# Blokkskjema.net
KiCad netlist of a schematic drawn in Altium Designer
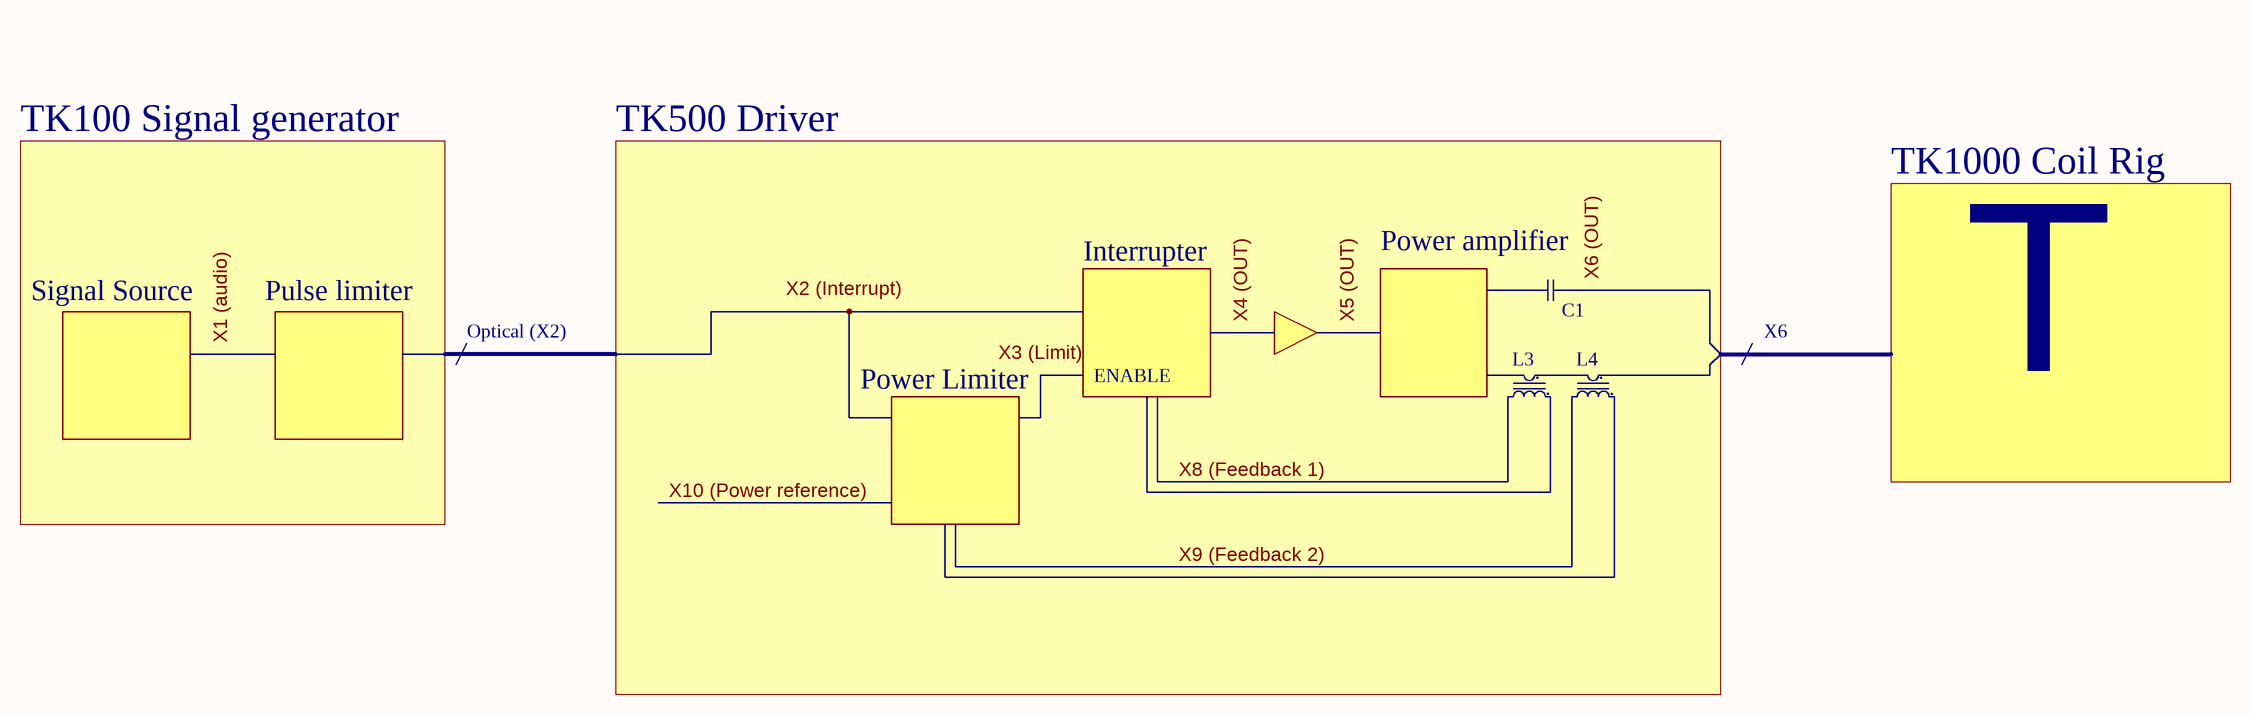
[diagram p0: Blokkskjema.SchDoc]

(export (version "E")
  (design (tool "Eeschema 10.0.6"))
  (components
    (comp (ref "C1")
      (value "100nF")
      (footprint "CAPC0603(1608)55_N")
      (description "X7R 50V 5%")
      (libsource (lib "OVLib") (part "CAP"))
    )
    (comp (ref "L3")
      (value "CurrentSenseTransformer")
      (libsource (lib "OVLib") (part "Current_sensing_transformer"))
    )
    (comp (ref "L4")
      (value "CurrentSenseTransformer")
      (libsource (lib "OVLib") (part "Current_sensing_transformer"))
    )
  )
  (nets
    (net (code "7") (name "/X8 (Feedback 1)") (class "Default")
      (node (ref "L3") (pin "3") (pinfunction "3_3") (pintype "passive"))
    )
    (net (code "8") (name "/X9 (Feedback 2)") (class "Default")
      (node (ref "L4") (pin "3") (pinfunction "3_3") (pintype "passive"))
    )
    (net (code "10") (name "Net-(C1-Pad1)") (class "Default")
      (node (ref "C1") (pin "1") (pinfunction "1_1") (pintype "passive"))
      (node (ref "L4") (pin "2") (pinfunction "2_2") (pintype "passive"))
    )
    (net (code "11") (name "Net-(L3-Pad2)") (class "Default")
      (node (ref "L3") (pin "2") (pinfunction "2_2") (pintype "passive"))
      (node (ref "L4") (pin "1") (pinfunction "1_1") (pintype "passive"))
    )
    (net (code "12") (name "unconnected-(C1-Pad2)") (class "Default")
      (node (ref "C1") (pin "2") (pinfunction "2_2") (pintype "passive"))
    )
    (net (code "13") (name "unconnected-(L3-Pad1)") (class "Default")
      (node (ref "L3") (pin "1") (pinfunction "1_1") (pintype "passive"))
    )
    (net (code "14") (name "unconnected-(L3-Pad4)") (class "Default")
      (node (ref "L3") (pin "4") (pinfunction "4_4") (pintype "passive"))
    )
    (net (code "15") (name "unconnected-(L4-Pad4)") (class "Default")
      (node (ref "L4") (pin "4") (pinfunction "4_4") (pintype "passive"))
    )
  )
)
